# ADC.net
KiCad netlist of a schematic drawn in Altium Designer
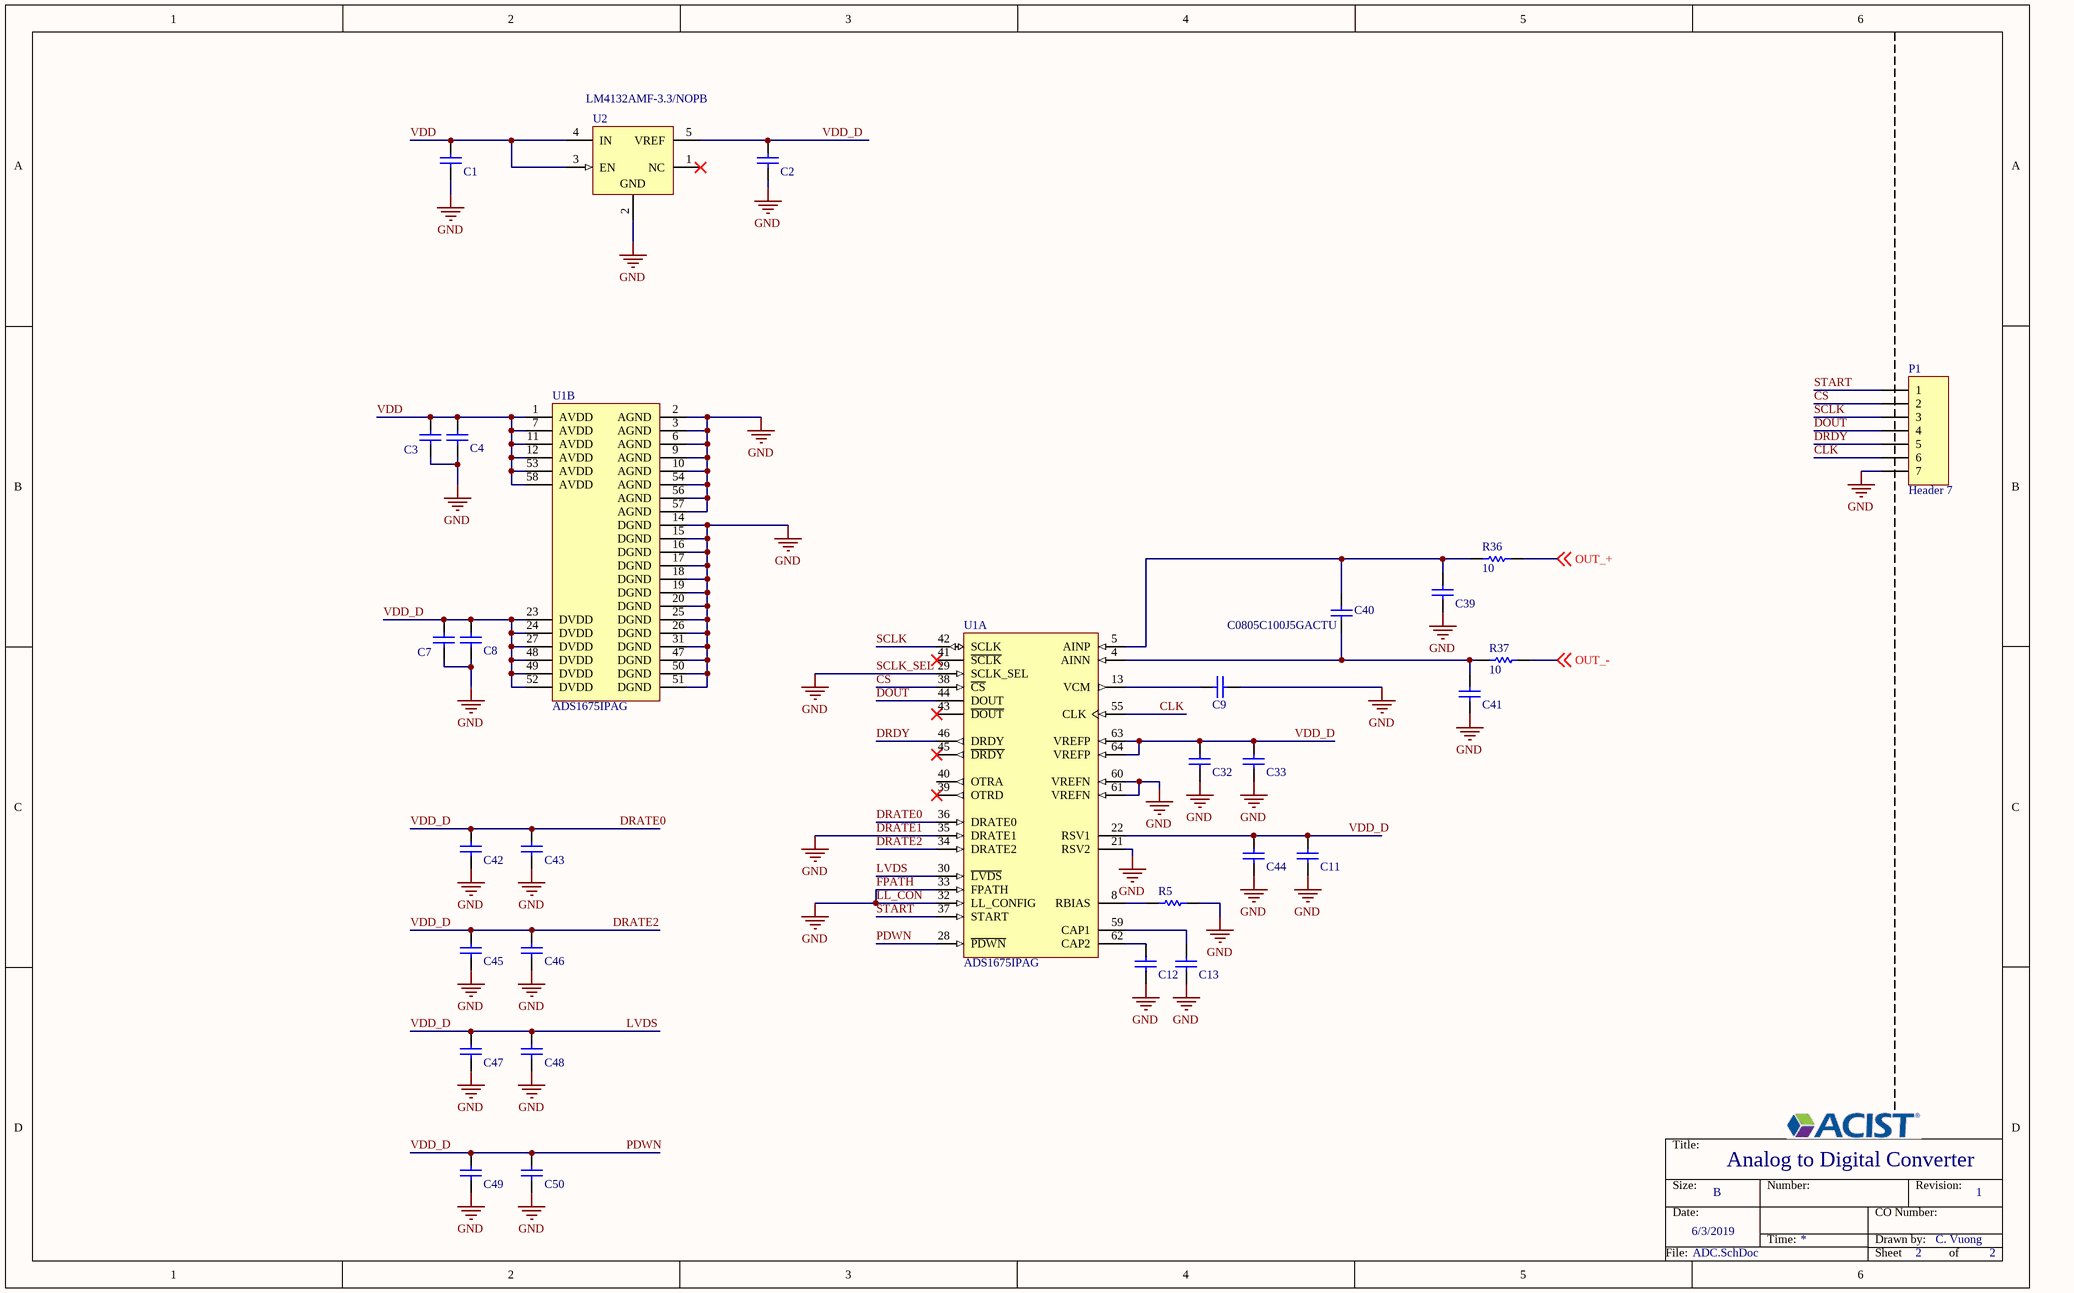
[diagram p0: ADC.SchDoc]

(export (version "E")
  (design (tool "Eeschema 10.0.6"))
  (components
    (comp (ref "C1")
      (value "C1608X5R1A106K080AC")
      (footprint "CAPC1608X90X20ML10")
      (description "Chip Capacitor, 10 uF, +/- 10%, 10 V, -55 to 85 degC, 0603 (1608 Metric), RoHS, Tape and Reel")
      (fields
        (field (name "PCN PART NUMBER") "MLCCPartNumberChange30/Nov/2012")
        (field (name "TOLERANCE") "±10%")
      )
      (libsource (lib "Altium Content Vault") (part "CAP-NP-2"))
    )
    (comp (ref "C2")
      (value "C1608X5R1A106K080AC")
      (footprint "CAPC1608X90X20ML10")
      (description "Chip Capacitor, 10 uF, +/- 10%, 10 V, -55 to 85 degC, 0603 (1608 Metric), RoHS, Tape and Reel")
      (fields
        (field (name "PCN PART NUMBER") "MLCCPartNumberChange30/Nov/2012")
        (field (name "TOLERANCE") "±10%")
      )
      (libsource (lib "Altium Content Vault") (part "CAP-NP-2"))
    )
    (comp (ref "C3")
      (value "C1608X5R1A106K080AC")
      (footprint "CAPC1608X90X20ML10")
      (description "Chip Capacitor, 10 uF, +/- 10%, 10 V, -55 to 85 degC, 0603 (1608 Metric), RoHS, Tape and Reel")
      (fields
        (field (name "PCN PART NUMBER") "MLCCPartNumberChange30/Nov/2012")
        (field (name "TOLERANCE") "±10%")
      )
      (libsource (lib "Altium Content Vault") (part "CAP-NP-2"))
    )
    (comp (ref "C4")
      (value "C1608X5R1A106K080AC")
      (footprint "CAPC1608X90X20ML10")
      (description "Chip Capacitor, 10 uF, +/- 10%, 10 V, -55 to 85 degC, 0603 (1608 Metric), RoHS, Tape and Reel")
      (fields
        (field (name "PCN PART NUMBER") "MLCCPartNumberChange30/Nov/2012")
        (field (name "TOLERANCE") "±10%")
      )
      (libsource (lib "Altium Content Vault") (part "CAP-NP-2"))
    )
    (comp (ref "C7")
      (value "C1608X5R1A106K080AC")
      (footprint "CAPC1608X90X20ML10")
      (description "Chip Capacitor, 10 uF, +/- 10%, 10 V, -55 to 85 degC, 0603 (1608 Metric), RoHS, Tape and Reel")
      (fields
        (field (name "PCN PART NUMBER") "MLCCPartNumberChange30/Nov/2012")
        (field (name "TOLERANCE") "±10%")
      )
      (libsource (lib "Altium Content Vault") (part "CAP-NP-2"))
    )
    (comp (ref "C8")
      (value "C1608X5R1A106K080AC")
      (footprint "CAPC1608X90X20ML10")
      (description "Chip Capacitor, 10 uF, +/- 10%, 10 V, -55 to 85 degC, 0603 (1608 Metric), RoHS, Tape and Reel")
      (fields
        (field (name "PCN PART NUMBER") "MLCCPartNumberChange30/Nov/2012")
        (field (name "TOLERANCE") "±10%")
      )
      (libsource (lib "Altium Content Vault") (part "CAP-NP-2"))
    )
    (comp (ref "C9")
      (value "C1608X5R1A106K080AC")
      (footprint "CAPC1608X90X20ML10")
      (description "Chip Capacitor, 10 uF, +/- 10%, 10 V, -55 to 85 degC, 0603 (1608 Metric), RoHS, Tape and Reel")
      (fields
        (field (name "PCN PART NUMBER") "MLCCPartNumberChange30/Nov/2012")
        (field (name "TOLERANCE") "±10%")
      )
      (libsource (lib "Altium Content Vault") (part "CAP-NP-2"))
    )
    (comp (ref "C11")
      (value "C1608X5R1A106K080AC")
      (footprint "CAPC1608X90X20ML10")
      (description "Chip Capacitor, 10 uF, +/- 10%, 10 V, -55 to 85 degC, 0603 (1608 Metric), RoHS, Tape and Reel")
      (fields
        (field (name "PCN PART NUMBER") "MLCCPartNumberChange30/Nov/2012")
        (field (name "TOLERANCE") "±10%")
      )
      (libsource (lib "Altium Content Vault") (part "CAP-NP-2"))
    )
    (comp (ref "C12")
      (value "C1608X5R1A106K080AC")
      (footprint "CAPC1608X90X20ML10")
      (description "Chip Capacitor, 10 uF, +/- 10%, 10 V, -55 to 85 degC, 0603 (1608 Metric), RoHS, Tape and Reel")
      (fields
        (field (name "PCN PART NUMBER") "MLCCPartNumberChange30/Nov/2012")
        (field (name "TOLERANCE") "±10%")
      )
      (libsource (lib "Altium Content Vault") (part "CAP-NP-2"))
    )
    (comp (ref "C13")
      (value "C1608X5R1A106K080AC")
      (footprint "CAPC1608X90X20ML10")
      (description "Chip Capacitor, 10 uF, +/- 10%, 10 V, -55 to 85 degC, 0603 (1608 Metric), RoHS, Tape and Reel")
      (fields
        (field (name "PCN PART NUMBER") "MLCCPartNumberChange30/Nov/2012")
        (field (name "TOLERANCE") "±10%")
      )
      (libsource (lib "Altium Content Vault") (part "CAP-NP-2"))
    )
    (comp (ref "C32")
      (value "C1608X5R1A106K080AC")
      (footprint "CAPC1608X90X20ML10")
      (description "Chip Capacitor, 10 uF, +/- 10%, 10 V, -55 to 85 degC, 0603 (1608 Metric), RoHS, Tape and Reel")
      (fields
        (field (name "PCN PART NUMBER") "MLCCPartNumberChange30/Nov/2012")
        (field (name "TOLERANCE") "±10%")
      )
      (libsource (lib "Altium Content Vault") (part "CAP-NP-2"))
    )
    (comp (ref "C33")
      (value "C1608X5R1A106K080AC")
      (footprint "CAPC1608X90X20ML10")
      (description "Chip Capacitor, 10 uF, +/- 10%, 10 V, -55 to 85 degC, 0603 (1608 Metric), RoHS, Tape and Reel")
      (fields
        (field (name "PCN PART NUMBER") "MLCCPartNumberChange30/Nov/2012")
        (field (name "TOLERANCE") "±10%")
      )
      (libsource (lib "Altium Content Vault") (part "CAP-NP-2"))
    )
    (comp (ref "C39")
      (value "C1608X5R1A106K080AC")
      (footprint "CAPC1608X90X20ML10")
      (description "Chip Capacitor, 10 uF, +/- 10%, 10 V, -55 to 85 degC, 0603 (1608 Metric), RoHS, Tape and Reel")
      (fields
        (field (name "PCN PART NUMBER") "MLCCPartNumberChange30/Nov/2012")
        (field (name "TOLERANCE") "±10%")
      )
      (libsource (lib "Altium Content Vault") (part "CAP-NP-2"))
    )
    (comp (ref "C40")
      (value "C0805C100J5GACTU")
      (footprint "CAPC2013X88X50LL20T25")
      (fields (field (name "MANUFACTURER") "Kemet"))
      (libsource (lib "Altium Content Vault") (part "CAP"))
    )
    (comp (ref "C41")
      (value "C1608X5R1A106K080AC")
      (footprint "CAPC1608X90X20ML10")
      (description "Chip Capacitor, 10 uF, +/- 10%, 10 V, -55 to 85 degC, 0603 (1608 Metric), RoHS, Tape and Reel")
      (fields
        (field (name "PCN PART NUMBER") "MLCCPartNumberChange30/Nov/2012")
        (field (name "TOLERANCE") "±10%")
      )
      (libsource (lib "Altium Content Vault") (part "CAP-NP-2"))
    )
    (comp (ref "C42")
      (value "C1608X5R1A106K080AC")
      (footprint "CAPC1608X90X20ML10")
      (description "Chip Capacitor, 10 uF, +/- 10%, 10 V, -55 to 85 degC, 0603 (1608 Metric), RoHS, Tape and Reel")
      (fields
        (field (name "PCN PART NUMBER") "MLCCPartNumberChange30/Nov/2012")
        (field (name "TOLERANCE") "±10%")
      )
      (libsource (lib "Altium Content Vault") (part "CAP-NP-2"))
    )
    (comp (ref "C43")
      (value "C1608X5R1A106K080AC")
      (footprint "CAPC1608X90X20ML10")
      (description "Chip Capacitor, 10 uF, +/- 10%, 10 V, -55 to 85 degC, 0603 (1608 Metric), RoHS, Tape and Reel")
      (fields
        (field (name "PCN PART NUMBER") "MLCCPartNumberChange30/Nov/2012")
        (field (name "TOLERANCE") "±10%")
      )
      (libsource (lib "Altium Content Vault") (part "CAP-NP-2"))
    )
    (comp (ref "C44")
      (value "C1608X5R1A106K080AC")
      (footprint "CAPC1608X90X20ML10")
      (description "Chip Capacitor, 10 uF, +/- 10%, 10 V, -55 to 85 degC, 0603 (1608 Metric), RoHS, Tape and Reel")
      (fields
        (field (name "PCN PART NUMBER") "MLCCPartNumberChange30/Nov/2012")
        (field (name "TOLERANCE") "±10%")
      )
      (libsource (lib "Altium Content Vault") (part "CAP-NP-2"))
    )
    (comp (ref "C45")
      (value "C1608X5R1A106K080AC")
      (footprint "CAPC1608X90X20ML10")
      (description "Chip Capacitor, 10 uF, +/- 10%, 10 V, -55 to 85 degC, 0603 (1608 Metric), RoHS, Tape and Reel")
      (fields
        (field (name "PCN PART NUMBER") "MLCCPartNumberChange30/Nov/2012")
        (field (name "TOLERANCE") "±10%")
      )
      (libsource (lib "Altium Content Vault") (part "CAP-NP-2"))
    )
    (comp (ref "C46")
      (value "C1608X5R1A106K080AC")
      (footprint "CAPC1608X90X20ML10")
      (description "Chip Capacitor, 10 uF, +/- 10%, 10 V, -55 to 85 degC, 0603 (1608 Metric), RoHS, Tape and Reel")
      (fields
        (field (name "PCN PART NUMBER") "MLCCPartNumberChange30/Nov/2012")
        (field (name "TOLERANCE") "±10%")
      )
      (libsource (lib "Altium Content Vault") (part "CAP-NP-2"))
    )
    (comp (ref "C47")
      (value "C1608X5R1A106K080AC")
      (footprint "CAPC1608X90X20ML10")
      (description "Chip Capacitor, 10 uF, +/- 10%, 10 V, -55 to 85 degC, 0603 (1608 Metric), RoHS, Tape and Reel")
      (fields
        (field (name "PCN PART NUMBER") "MLCCPartNumberChange30/Nov/2012")
        (field (name "TOLERANCE") "±10%")
      )
      (libsource (lib "Altium Content Vault") (part "CAP-NP-2"))
    )
    (comp (ref "C48")
      (value "C1608X5R1A106K080AC")
      (footprint "CAPC1608X90X20ML10")
      (description "Chip Capacitor, 10 uF, +/- 10%, 10 V, -55 to 85 degC, 0603 (1608 Metric), RoHS, Tape and Reel")
      (fields
        (field (name "PCN PART NUMBER") "MLCCPartNumberChange30/Nov/2012")
        (field (name "TOLERANCE") "±10%")
      )
      (libsource (lib "Altium Content Vault") (part "CAP-NP-2"))
    )
    (comp (ref "C49")
      (value "C1608X5R1A106K080AC")
      (footprint "CAPC1608X90X20ML10")
      (description "Chip Capacitor, 10 uF, +/- 10%, 10 V, -55 to 85 degC, 0603 (1608 Metric), RoHS, Tape and Reel")
      (fields
        (field (name "PCN PART NUMBER") "MLCCPartNumberChange30/Nov/2012")
        (field (name "TOLERANCE") "±10%")
      )
      (libsource (lib "Altium Content Vault") (part "CAP-NP-2"))
    )
    (comp (ref "C50")
      (value "C1608X5R1A106K080AC")
      (footprint "CAPC1608X90X20ML10")
      (description "Chip Capacitor, 10 uF, +/- 10%, 10 V, -55 to 85 degC, 0603 (1608 Metric), RoHS, Tape and Reel")
      (fields
        (field (name "PCN PART NUMBER") "MLCCPartNumberChange30/Nov/2012")
        (field (name "TOLERANCE") "±10%")
      )
      (libsource (lib "Altium Content Vault") (part "CAP-NP-2"))
    )
    (comp (ref "P1")
      (value "Header 7")
      (footprint "HDR1X7")
      (description "Header, 7-Pin")
      (fields (field (name "PUBLISHER") "Altium Limited"))
      (libsource (lib "Miscellaneous Connectors") (part "Header 7"))
    )
    (comp (ref "R5")
      (value "RR0816P-241-D")
      (footprint "RESC1608X50X30LL20T20")
      (fields (field (name "MANUFACTURER") "Susumu"))
      (libsource (lib "Altium Content Vault") (part "RES"))
    )
    (comp (ref "R36")
      (value "10")
      (footprint "RESC1608X50X30LL20T20")
      (fields (field (name "PART NUMBER") "RR0816P-241-D") (field (name "MANUFACTURER") "Susumu"))
      (libsource (lib "Altium Content Vault") (part "RES"))
    )
    (comp (ref "R37")
      (value "10")
      (footprint "RESC1608X50X30LL20T20")
      (fields (field (name "PART NUMBER") "RR0816P-241-D") (field (name "MANUFACTURER") "Susumu"))
      (libsource (lib "Altium Content Vault") (part "RES"))
    )
    (comp (ref "U1")
      (value "ADS1675IPAG")
      (footprint "TI-PAG64_L")
      (description "4 MSPS, 24-Bit ADC, -40 to 85 degC, 64-pin QFP (PAG64), Green (RoHS & no Sb/Br)")
      (fields (field (name "MANUFACTURER") "Texas Instruments"))
      (libsource (lib "Project X_1") (part "TI-ADS1675PAG64"))
    )
    (comp (ref "U2")
      (value "LM4132AMF-3.3/NOPB")
      (footprint "DBV0005A_L")
      (description "Precision Low Dropout Voltage Reference, 5-pin SOT-23, Pb-Free")
      (fields (field (name "MANUFACTURER") "Texas Instruments"))
      (libsource (lib "Altium Content Vault") (part "PM-REF-LM4128-SOT5"))
    )
  )
  (nets
    (net (code "1") (name "/CLK") (class "Default")
      (node (ref "P1") (pin "6") (pinfunction "6_6") (pintype "passive"))
      (node (ref "U1") (pin "55") (pinfunction "CLK_55") (pintype "input"))
    )
    (net (code "2") (name "/CS") (class "Default")
      (node (ref "P1") (pin "2") (pinfunction "2_2") (pintype "passive"))
      (node (ref "U1") (pin "38") (pinfunction "~{CS}_38") (pintype "input"))
    )
    (net (code "3") (name "/DOUT") (class "Default")
      (node (ref "P1") (pin "4") (pinfunction "4_4") (pintype "passive"))
      (node (ref "U1") (pin "44") (pinfunction "DOUT_44") (pintype "tri_state"))
    )
    (net (code "4") (name "/DRATE0") (class "Default")
      (node (ref "C11") (pin "1") (pinfunction "1_1") (pintype "passive"))
      (node (ref "C2") (pin "1") (pinfunction "1_1") (pintype "passive"))
      (node (ref "C32") (pin "1") (pinfunction "1_1") (pintype "passive"))
      (node (ref "C33") (pin "1") (pinfunction "1_1") (pintype "passive"))
      (node (ref "C42") (pin "1") (pinfunction "1_1") (pintype "passive"))
      (node (ref "C43") (pin "1") (pinfunction "1_1") (pintype "passive"))
      (node (ref "C44") (pin "1") (pinfunction "1_1") (pintype "passive"))
      (node (ref "C45") (pin "1") (pinfunction "1_1") (pintype "passive"))
      (node (ref "C46") (pin "1") (pinfunction "1_1") (pintype "passive"))
      (node (ref "C47") (pin "1") (pinfunction "1_1") (pintype "passive"))
      (node (ref "C48") (pin "1") (pinfunction "1_1") (pintype "passive"))
      (node (ref "C49") (pin "1") (pinfunction "1_1") (pintype "passive"))
      (node (ref "C50") (pin "1") (pinfunction "1_1") (pintype "passive"))
      (node (ref "C7") (pin "1") (pinfunction "1_1") (pintype "passive"))
      (node (ref "C8") (pin "1") (pinfunction "1_1") (pintype "passive"))
      (node (ref "U1") (pin "22") (pinfunction "RSV1_22") (pintype "passive"))
      (node (ref "U1") (pin "23") (pinfunction "DVDD_23") (pintype "power_in"))
      (node (ref "U1") (pin "24") (pinfunction "DVDD_24") (pintype "power_in"))
      (node (ref "U1") (pin "27") (pinfunction "DVDD_27") (pintype "power_in"))
      (node (ref "U1") (pin "28") (pinfunction "~{PDWN}_28") (pintype "input"))
      (node (ref "U1") (pin "30") (pinfunction "~{LVDS}_30") (pintype "input"))
      (node (ref "U1") (pin "34") (pinfunction "DRATE2_34") (pintype "input"))
      (node (ref "U1") (pin "36") (pinfunction "DRATE0_36") (pintype "input"))
      (node (ref "U1") (pin "48") (pinfunction "DVDD_48") (pintype "power_in"))
      (node (ref "U1") (pin "49") (pinfunction "DVDD_49") (pintype "power_in"))
      (node (ref "U1") (pin "52") (pinfunction "DVDD_52") (pintype "power_in"))
      (node (ref "U1") (pin "63") (pinfunction "VREFP_63") (pintype "input"))
      (node (ref "U1") (pin "64") (pinfunction "VREFP_64") (pintype "input"))
      (node (ref "U2") (pin "5") (pinfunction "VREF_5") (pintype "power_in"))
    )
    (net (code "5") (name "/DRDY") (class "Default")
      (node (ref "P1") (pin "5") (pinfunction "5_5") (pintype "passive"))
      (node (ref "U1") (pin "46") (pinfunction "DRDY_46") (pintype "output"))
    )
    (net (code "6") (name "/SCLK") (class "Default")
      (node (ref "P1") (pin "3") (pinfunction "3_3") (pintype "passive"))
      (node (ref "U1") (pin "42") (pinfunction "SCLK_42") (pintype "bidirectional"))
    )
    (net (code "7") (name "/START") (class "Default")
      (node (ref "P1") (pin "1") (pinfunction "1_1") (pintype "passive"))
      (node (ref "U1") (pin "37") (pinfunction "START_37") (pintype "input"))
    )
    (net (code "8") (name "/VDD") (class "Default")
      (node (ref "C1") (pin "1") (pinfunction "1_1") (pintype "passive"))
      (node (ref "C3") (pin "1") (pinfunction "1_1") (pintype "passive"))
      (node (ref "C4") (pin "1") (pinfunction "1_1") (pintype "passive"))
      (node (ref "U1") (pin "1") (pinfunction "AVDD_1") (pintype "power_in"))
      (node (ref "U1") (pin "11") (pinfunction "AVDD_11") (pintype "power_in"))
      (node (ref "U1") (pin "12") (pinfunction "AVDD_12") (pintype "power_in"))
      (node (ref "U1") (pin "53") (pinfunction "AVDD_53") (pintype "power_in"))
      (node (ref "U1") (pin "58") (pinfunction "AVDD_58") (pintype "power_in"))
      (node (ref "U1") (pin "7") (pinfunction "AVDD_7") (pintype "power_in"))
      (node (ref "U2") (pin "3") (pinfunction "EN_3") (pintype "input"))
      (node (ref "U2") (pin "4") (pinfunction "IN_4") (pintype "power_in"))
    )
    (net (code "9") (name "GND") (class "Default")
      (node (ref "C1") (pin "2") (pinfunction "2_2") (pintype "passive"))
      (node (ref "C11") (pin "2") (pinfunction "2_2") (pintype "passive"))
      (node (ref "C12") (pin "2") (pinfunction "2_2") (pintype "passive"))
      (node (ref "C13") (pin "2") (pinfunction "2_2") (pintype "passive"))
      (node (ref "C2") (pin "2") (pinfunction "2_2") (pintype "passive"))
      (node (ref "C3") (pin "2") (pinfunction "2_2") (pintype "passive"))
      (node (ref "C32") (pin "2") (pinfunction "2_2") (pintype "passive"))
      (node (ref "C33") (pin "2") (pinfunction "2_2") (pintype "passive"))
      (node (ref "C39") (pin "2") (pinfunction "2_2") (pintype "passive"))
      (node (ref "C4") (pin "2") (pinfunction "2_2") (pintype "passive"))
      (node (ref "C41") (pin "2") (pinfunction "2_2") (pintype "passive"))
      (node (ref "C42") (pin "2") (pinfunction "2_2") (pintype "passive"))
      (node (ref "C43") (pin "2") (pinfunction "2_2") (pintype "passive"))
      (node (ref "C44") (pin "2") (pinfunction "2_2") (pintype "passive"))
      (node (ref "C45") (pin "2") (pinfunction "2_2") (pintype "passive"))
      (node (ref "C46") (pin "2") (pinfunction "2_2") (pintype "passive"))
      (node (ref "C47") (pin "2") (pinfunction "2_2") (pintype "passive"))
      (node (ref "C48") (pin "2") (pinfunction "2_2") (pintype "passive"))
      (node (ref "C49") (pin "2") (pinfunction "2_2") (pintype "passive"))
      (node (ref "C50") (pin "2") (pinfunction "2_2") (pintype "passive"))
      (node (ref "C7") (pin "2") (pinfunction "2_2") (pintype "passive"))
      (node (ref "C8") (pin "2") (pinfunction "2_2") (pintype "passive"))
      (node (ref "C9") (pin "2") (pinfunction "2_2") (pintype "passive"))
      (node (ref "P1") (pin "7") (pinfunction "7_7") (pintype "passive"))
      (node (ref "R5") (pin "2") (pinfunction "2_2") (pintype "passive"))
      (node (ref "U1") (pin "10") (pinfunction "AGND_10") (pintype "power_in"))
      (node (ref "U1") (pin "14") (pinfunction "DGND_14") (pintype "power_in"))
      (node (ref "U1") (pin "15") (pinfunction "DGND_15") (pintype "power_in"))
      (node (ref "U1") (pin "16") (pinfunction "DGND_16") (pintype "power_in"))
      (node (ref "U1") (pin "17") (pinfunction "DGND_17") (pintype "power_in"))
      (node (ref "U1") (pin "18") (pinfunction "DGND_18") (pintype "power_in"))
      (node (ref "U1") (pin "19") (pinfunction "DGND_19") (pintype "power_in"))
      (node (ref "U1") (pin "2") (pinfunction "AGND_2") (pintype "power_in"))
      (node (ref "U1") (pin "20") (pinfunction "DGND_20") (pintype "power_in"))
      (node (ref "U1") (pin "21") (pinfunction "RSV2_21") (pintype "passive"))
      (node (ref "U1") (pin "25") (pinfunction "DGND_25") (pintype "power_in"))
      (node (ref "U1") (pin "26") (pinfunction "DGND_26") (pintype "power_in"))
      (node (ref "U1") (pin "29") (pinfunction "SCLK_SEL_29") (pintype "input"))
      (node (ref "U1") (pin "3") (pinfunction "AGND_3") (pintype "power_in"))
      (node (ref "U1") (pin "31") (pinfunction "DGND_31") (pintype "power_in"))
      (node (ref "U1") (pin "32") (pinfunction "LL_CONFIG_32") (pintype "input"))
      (node (ref "U1") (pin "33") (pinfunction "FPATH_33") (pintype "input"))
      (node (ref "U1") (pin "35") (pinfunction "DRATE1_35") (pintype "input"))
      (node (ref "U1") (pin "47") (pinfunction "DGND_47") (pintype "power_in"))
      (node (ref "U1") (pin "50") (pinfunction "DGND_50") (pintype "power_in"))
      (node (ref "U1") (pin "51") (pinfunction "DGND_51") (pintype "power_in"))
      (node (ref "U1") (pin "54") (pinfunction "AGND_54") (pintype "power_in"))
      (node (ref "U1") (pin "56") (pinfunction "AGND_56") (pintype "power_in"))
      (node (ref "U1") (pin "57") (pinfunction "AGND_57") (pintype "power_in"))
      (node (ref "U1") (pin "6") (pinfunction "AGND_6") (pintype "power_in"))
      (node (ref "U1") (pin "60") (pinfunction "VREFN_60") (pintype "input"))
      (node (ref "U1") (pin "61") (pinfunction "VREFN_61") (pintype "input"))
      (node (ref "U1") (pin "9") (pinfunction "AGND_9") (pintype "power_in"))
      (node (ref "U2") (pin "2") (pinfunction "GND_2") (pintype "power_in"))
    )
    (net (code "10") (name "Net-(U1A-AINN)") (class "Default")
      (node (ref "C40") (pin "1") (pinfunction "1_1") (pintype "passive"))
      (node (ref "C41") (pin "1") (pinfunction "1_1") (pintype "passive"))
      (node (ref "R37") (pin "2") (pinfunction "2_2") (pintype "passive"))
      (node (ref "U1") (pin "4") (pinfunction "AINN_4") (pintype "input"))
    )
    (net (code "11") (name "Net-(U1A-AINP)") (class "Default")
      (node (ref "C39") (pin "1") (pinfunction "1_1") (pintype "passive"))
      (node (ref "C40") (pin "2") (pinfunction "2_2") (pintype "passive"))
      (node (ref "R36") (pin "2") (pinfunction "2_2") (pintype "passive"))
      (node (ref "U1") (pin "5") (pinfunction "AINP_5") (pintype "input"))
    )
    (net (code "12") (name "Net-(U1A-CAP1)") (class "Default")
      (node (ref "C13") (pin "1") (pinfunction "1_1") (pintype "passive"))
      (node (ref "U1") (pin "59") (pinfunction "CAP1_59") (pintype "passive"))
    )
    (net (code "13") (name "Net-(U1A-CAP2)") (class "Default")
      (node (ref "C12") (pin "1") (pinfunction "1_1") (pintype "passive"))
      (node (ref "U1") (pin "62") (pinfunction "CAP2_62") (pintype "passive"))
    )
    (net (code "14") (name "Net-(U1A-RBIAS)") (class "Default")
      (node (ref "R5") (pin "1") (pinfunction "1_1") (pintype "passive"))
      (node (ref "U1") (pin "8") (pinfunction "RBIAS_8") (pintype "passive"))
    )
    (net (code "15") (name "Net-(U1A-VCM)") (class "Default")
      (node (ref "C9") (pin "1") (pinfunction "1_1") (pintype "passive"))
      (node (ref "U1") (pin "13") (pinfunction "VCM_13") (pintype "output"))
    )
    (net (code "16") (name "OUT_+") (class "Default")
      (node (ref "R36") (pin "1") (pinfunction "1_1") (pintype "passive"))
    )
    (net (code "17") (name "OUT_-") (class "Default")
      (node (ref "R37") (pin "1") (pinfunction "1_1") (pintype "passive"))
    )
    (net (code "18") (name "unconnected-(U1A-OTRA-Pad40)") (class "Default")
      (node (ref "U1") (pin "40") (pinfunction "OTRA_40") (pintype "output"))
    )
    (net (code "19") (name "unconnected-(U1A-OTRD-Pad39)") (class "Default")
      (node (ref "U1") (pin "39") (pinfunction "OTRD_39") (pintype "output+no_connect"))
    )
    (net (code "20") (name "unconnected-(U1A-~{DOUT}-Pad43)") (class "Default")
      (node (ref "U1") (pin "43") (pinfunction "~{DOUT}_43") (pintype "tri_state+no_connect"))
    )
    (net (code "21") (name "unconnected-(U1A-~{DRDY}-Pad45)") (class "Default")
      (node (ref "U1") (pin "45") (pinfunction "~{DRDY}_45") (pintype "output+no_connect"))
    )
    (net (code "22") (name "unconnected-(U1A-~{SCLK}-Pad41)") (class "Default")
      (node (ref "U1") (pin "41") (pinfunction "~{SCLK}_41") (pintype "tri_state+no_connect"))
    )
    (net (code "23") (name "unconnected-(U2-NC-Pad1)") (class "Default")
      (node (ref "U2") (pin "1") (pinfunction "NC_1") (pintype "passive+no_connect"))
    )
  )
)
